# FPGA-Supply.net
KiCad netlist of a schematic drawn in Altium Designer
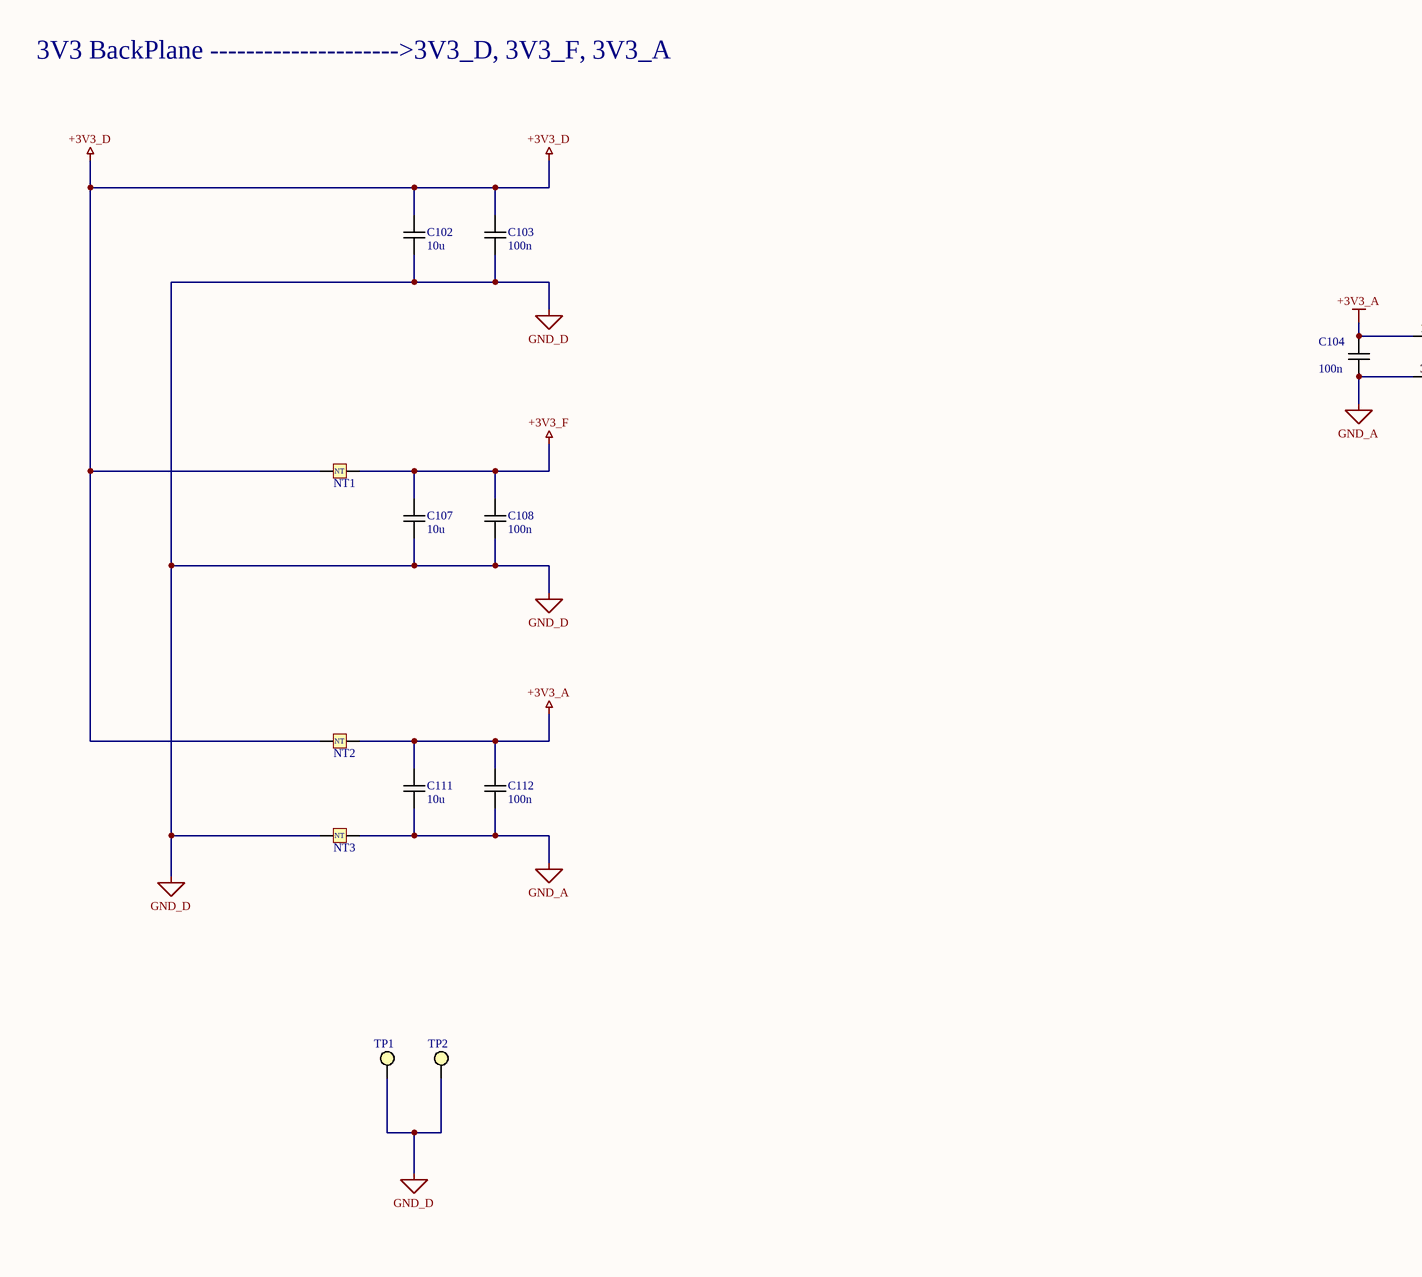
[diagram p0: FPGA-Supply.SchDoc, left]
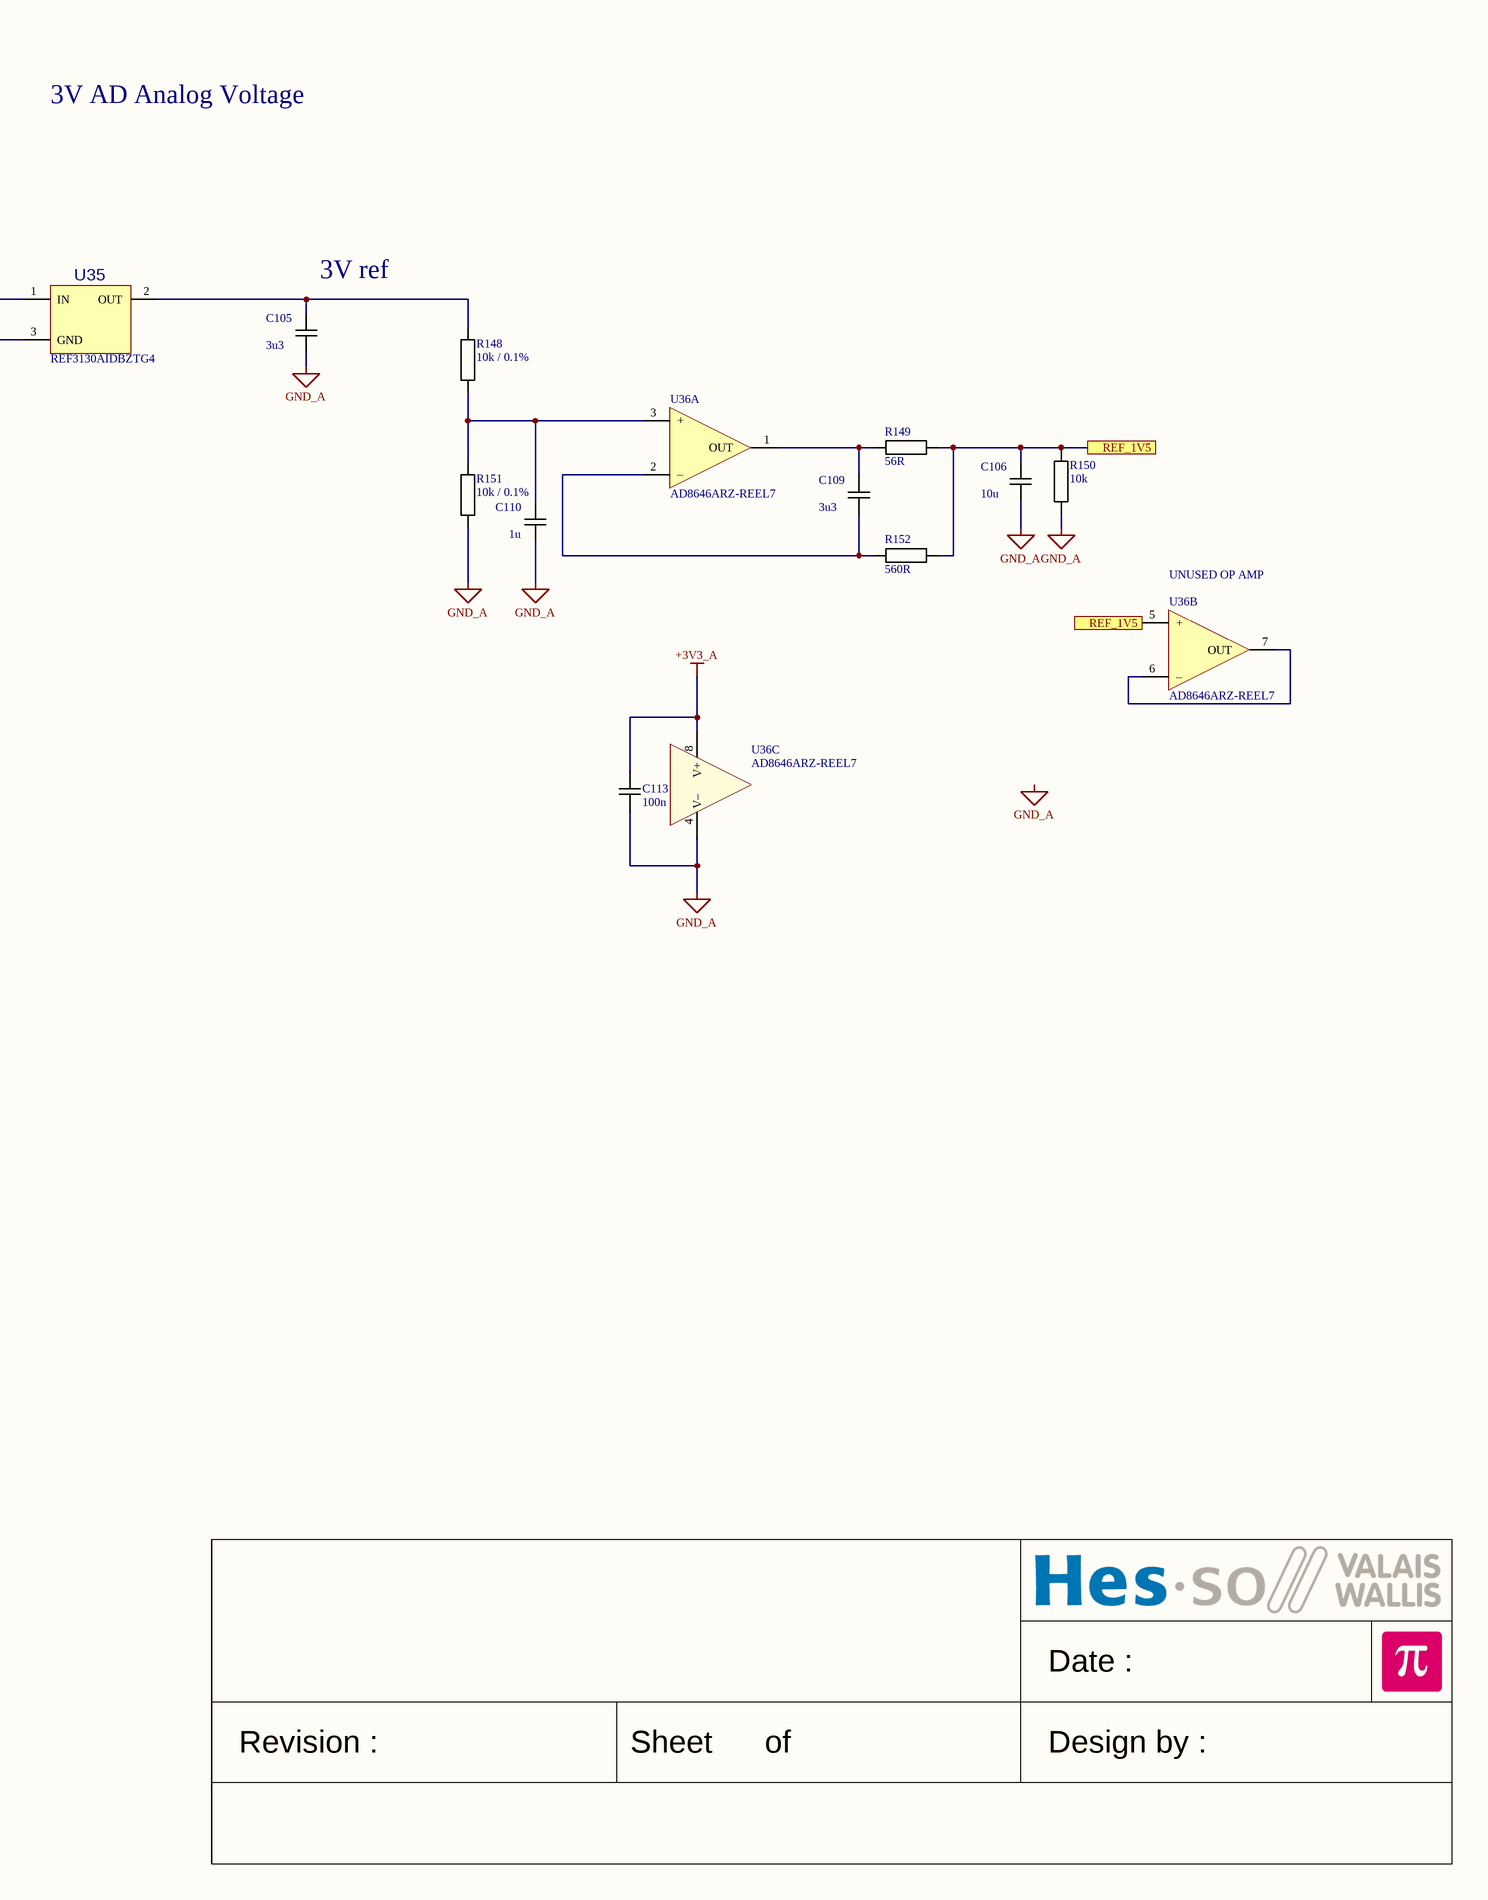
[diagram p1: FPGA-Supply.SchDoc, right]

(export (version "E")
  (design (tool "Eeschema 10.0.6"))
  (components
    (comp (ref "C102")
      (value "10u")
      (footprint "CAPACITOR 2012 REFLOW")
      (description "Capacitor X7R 10% 10V 2012(0805)")
      (libsource (lib "Capacitor") (part "Capacitor"))
    )
    (comp (ref "C103")
      (value "100n")
      (footprint "CAPACITOR 2012 REFLOW")
      (description "Capacitor X7R 10% 50V 2012(0805)")
      (libsource (lib "Capacitor") (part "Capacitor"))
    )
    (comp (ref "C104")
      (value "100n")
      (footprint "CAPACITOR 1608 REFLOW")
      (description "Capacitor X7R 10% 50V 1608(0603)")
      (libsource (lib "Capacitor") (part "Capacitor"))
    )
    (comp (ref "C105")
      (value "3u3")
      (footprint "CAPACITOR 2012 REFLOW")
      (description "Capacitor X7R 10% 10V 2012(0805)")
      (libsource (lib "Capacitor") (part "Capacitor"))
    )
    (comp (ref "C106")
      (value "10u")
      (footprint "CAPACITOR 2012 REFLOW")
      (description "Capacitor X7R 10% 10V 2012(0805)")
      (libsource (lib "Capacitor") (part "Capacitor"))
    )
    (comp (ref "C107")
      (value "10u")
      (footprint "CAPACITOR 2012 REFLOW")
      (description "Capacitor X7R 10% 10V 2012(0805)")
      (libsource (lib "Capacitor") (part "Capacitor"))
    )
    (comp (ref "C108")
      (value "100n")
      (footprint "CAPACITOR 2012 REFLOW")
      (description "Capacitor X7R 10% 50V 2012(0805)")
      (libsource (lib "Capacitor") (part "Capacitor"))
    )
    (comp (ref "C109")
      (value "3u3")
      (footprint "CAPACITOR 2012 REFLOW")
      (description "Capacitor X7R 10% 10V 2012(0805)")
      (libsource (lib "Capacitor") (part "Capacitor"))
    )
    (comp (ref "C110")
      (value "1u")
      (footprint "CAPACITOR 2012 REFLOW")
      (description "Capacitor X7R 10% 10V 2012(0805)")
      (libsource (lib "Capacitor") (part "Capacitor"))
    )
    (comp (ref "C111")
      (value "10u")
      (footprint "CAPACITOR 2012 REFLOW")
      (description "Capacitor X7R 10% 10V 2012(0805)")
      (libsource (lib "Capacitor") (part "Capacitor"))
    )
    (comp (ref "C112")
      (value "100n")
      (footprint "CAPACITOR 2012 REFLOW")
      (description "Capacitor X7R 10% 50V 2012(0805)")
      (libsource (lib "Capacitor") (part "Capacitor"))
    )
    (comp (ref "C113")
      (value "100n")
      (footprint "CAPACITOR 1608 REFLOW")
      (description "Capacitor X7R 10% 50V 1608(0603)")
      (libsource (lib "Capacitor") (part "Capacitor"))
    )
    (comp (ref "NT1")
      (value "Net Tie")
      (footprint "NET TIE 1005")
      (description "Connection for 2 different NETNAME")
      (libsource (lib "Jumper") (part "Net Tie"))
    )
    (comp (ref "NT2")
      (value "Net Tie")
      (footprint "NET TIE 1005")
      (description "Connection for 2 different NETNAME")
      (libsource (lib "Jumper") (part "Net Tie"))
    )
    (comp (ref "NT3")
      (value "Net Tie")
      (footprint "NET TIE 1005")
      (description "Connection for 2 different NETNAME")
      (libsource (lib "Jumper") (part "Net Tie"))
    )
    (comp (ref "R148")
      (value "10k / 0.1%")
      (footprint "RESISTOR 1608 REFLOW")
      (description "Resistor 1% 50V 100mW 1608(0603)")
      (libsource (lib "Resistor") (part "Resistor"))
    )
    (comp (ref "R149")
      (value "56R")
      (footprint "RESISTOR 1608 REFLOW")
      (description "Resistor 1% 50V 100mW 1608(0603)")
      (libsource (lib "Resistor") (part "Resistor"))
    )
    (comp (ref "R150")
      (value "10k")
      (footprint "RESISTOR 1608 REFLOW")
      (description "Resistor 1% 50V 100mW 1608(0603)")
      (libsource (lib "Resistor") (part "Resistor"))
    )
    (comp (ref "R151")
      (value "10k / 0.1%")
      (footprint "RESISTOR 1608 REFLOW")
      (description "Resistor 1% 50V 100mW 1608(0603)")
      (libsource (lib "Resistor") (part "Resistor"))
    )
    (comp (ref "R152")
      (value "560R")
      (footprint "RESISTOR 1608 REFLOW")
      (description "Resistor 1% 50V 100mW 1608(0603)")
      (libsource (lib "Resistor") (part "Resistor"))
    )
    (comp (ref "TP1")
      (value "*")
      (footprint "Test Point Keystone Miniature BLACK")
      (description "Test Point")
      (libsource (lib "Testpoint") (part "Test Point"))
    )
    (comp (ref "TP2")
      (value "*")
      (footprint "Test Point Keystone Miniature BLACK")
      (description "Test Point")
      (libsource (lib "Testpoint") (part "Test Point"))
    )
    (comp (ref "U35")
      (value "REF3130AIDBZTG4")
      (footprint "SOT23 P0.95 C1.6x3.0 H1.3")
      (description "Generic Positive Voltage Reference")
      (fields (field (name "MANUFACTURER") "Texas Instruments"))
      (libsource (lib "Regulator") (part "REFERENCE SOT23 IN-OUT- GND"))
    )
    (comp (ref "U36")
      (value "AD8646ARZ-REEL7")
      (footprint "SO8 P1.27 C4.0X5.0 H1.75")
      (description "Generic dual OPA 8 pins")
      (fields (field (name "MANUFACTURER") "Analog Devices"))
      (libsource (lib "Amplifier") (part "OPA DUAL"))
    )
  )
  (nets
    (net (code "1") (name "+3V3_A") (class "Default")
      (node (ref "C104") (pin "2") (pinfunction "2_2") (pintype "passive"))
      (node (ref "C111") (pin "1") (pinfunction "1_1") (pintype "passive"))
      (node (ref "C112") (pin "1") (pinfunction "1_1") (pintype "passive"))
      (node (ref "C113") (pin "2") (pinfunction "2_2") (pintype "passive"))
      (node (ref "NT2") (pin "2") (pinfunction "2_2") (pintype "passive"))
      (node (ref "U35") (pin "1") (pinfunction "IN_1") (pintype "passive"))
      (node (ref "U36") (pin "8") (pinfunction "V+_8") (pintype "passive"))
    )
    (net (code "2") (name "+3V3_D") (class "Default")
      (node (ref "C102") (pin "1") (pinfunction "1_1") (pintype "passive"))
      (node (ref "C103") (pin "1") (pinfunction "1_1") (pintype "passive"))
      (node (ref "NT1") (pin "1") (pinfunction "1_1") (pintype "passive"))
      (node (ref "NT2") (pin "1") (pinfunction "1_1") (pintype "passive"))
    )
    (net (code "3") (name "+3V3_F") (class "Default")
      (node (ref "C107") (pin "1") (pinfunction "1_1") (pintype "passive"))
      (node (ref "C108") (pin "1") (pinfunction "1_1") (pintype "passive"))
      (node (ref "NT1") (pin "2") (pinfunction "2_2") (pintype "passive"))
    )
    (net (code "4") (name "/REF_1V5") (class "Default")
      (node (ref "C106") (pin "2") (pinfunction "2_2") (pintype "passive"))
      (node (ref "R149") (pin "1") (pinfunction "1_1") (pintype "passive"))
      (node (ref "R150") (pin "1") (pinfunction "1_1") (pintype "passive"))
      (node (ref "R152") (pin "1") (pinfunction "1_1") (pintype "passive"))
      (node (ref "U36") (pin "5") (pinfunction "+_5") (pintype "passive"))
    )
    (net (code "5") (name "GND_A") (class "Default")
      (node (ref "C104") (pin "1") (pinfunction "1_1") (pintype "passive"))
      (node (ref "C105") (pin "1") (pinfunction "1_1") (pintype "passive"))
      (node (ref "C106") (pin "1") (pinfunction "1_1") (pintype "passive"))
      (node (ref "C110") (pin "1") (pinfunction "1_1") (pintype "passive"))
      (node (ref "C111") (pin "2") (pinfunction "2_2") (pintype "passive"))
      (node (ref "C112") (pin "2") (pinfunction "2_2") (pintype "passive"))
      (node (ref "C113") (pin "1") (pinfunction "1_1") (pintype "passive"))
      (node (ref "NT3") (pin "2") (pinfunction "2_2") (pintype "passive"))
      (node (ref "R150") (pin "2") (pinfunction "2_2") (pintype "passive"))
      (node (ref "R151") (pin "2") (pinfunction "2_2") (pintype "passive"))
      (node (ref "U35") (pin "3") (pinfunction "GND_3") (pintype "passive"))
      (node (ref "U36") (pin "4") (pinfunction "V–_4") (pintype "passive"))
    )
    (net (code "6") (name "GND_D") (class "Default")
      (node (ref "C102") (pin "2") (pinfunction "2_2") (pintype "passive"))
      (node (ref "C103") (pin "2") (pinfunction "2_2") (pintype "passive"))
      (node (ref "C107") (pin "2") (pinfunction "2_2") (pintype "passive"))
      (node (ref "C108") (pin "2") (pinfunction "2_2") (pintype "passive"))
      (node (ref "NT3") (pin "1") (pinfunction "1_1") (pintype "passive"))
      (node (ref "TP1") (pin "1") (pinfunction "1_1") (pintype "passive"))
      (node (ref "TP2") (pin "1") (pinfunction "1_1") (pintype "passive"))
    )
    (net (code "7") (name "Net-(U35-OUT)") (class "Default")
      (node (ref "C105") (pin "2") (pinfunction "2_2") (pintype "passive"))
      (node (ref "R148") (pin "2") (pinfunction "2_2") (pintype "passive"))
      (node (ref "U35") (pin "2") (pinfunction "OUT_2") (pintype "passive"))
    )
    (net (code "8") (name "Net-(U36A-+)") (class "Default")
      (node (ref "C110") (pin "2") (pinfunction "2_2") (pintype "passive"))
      (node (ref "R148") (pin "1") (pinfunction "1_1") (pintype "passive"))
      (node (ref "R151") (pin "1") (pinfunction "1_1") (pintype "passive"))
      (node (ref "U36") (pin "3") (pinfunction "+_3") (pintype "passive"))
    )
    (net (code "9") (name "Net-(U36A-OUT)") (class "Default")
      (node (ref "C109") (pin "2") (pinfunction "2_2") (pintype "passive"))
      (node (ref "R149") (pin "2") (pinfunction "2_2") (pintype "passive"))
      (node (ref "U36") (pin "1") (pinfunction "OUT_1") (pintype "passive"))
    )
    (net (code "10") (name "Net-(U36A-–)") (class "Default")
      (node (ref "C109") (pin "1") (pinfunction "1_1") (pintype "passive"))
      (node (ref "R152") (pin "2") (pinfunction "2_2") (pintype "passive"))
      (node (ref "U36") (pin "2") (pinfunction "–_2") (pintype "passive"))
    )
    (net (code "11") (name "Net-(U36B-OUT)") (class "Default")
      (node (ref "U36") (pin "6") (pinfunction "–_6") (pintype "passive"))
      (node (ref "U36") (pin "7") (pinfunction "OUT_7") (pintype "passive"))
    )
  )
)
